# Sheet2.net
KiCad netlist of a schematic drawn in Altium Designer
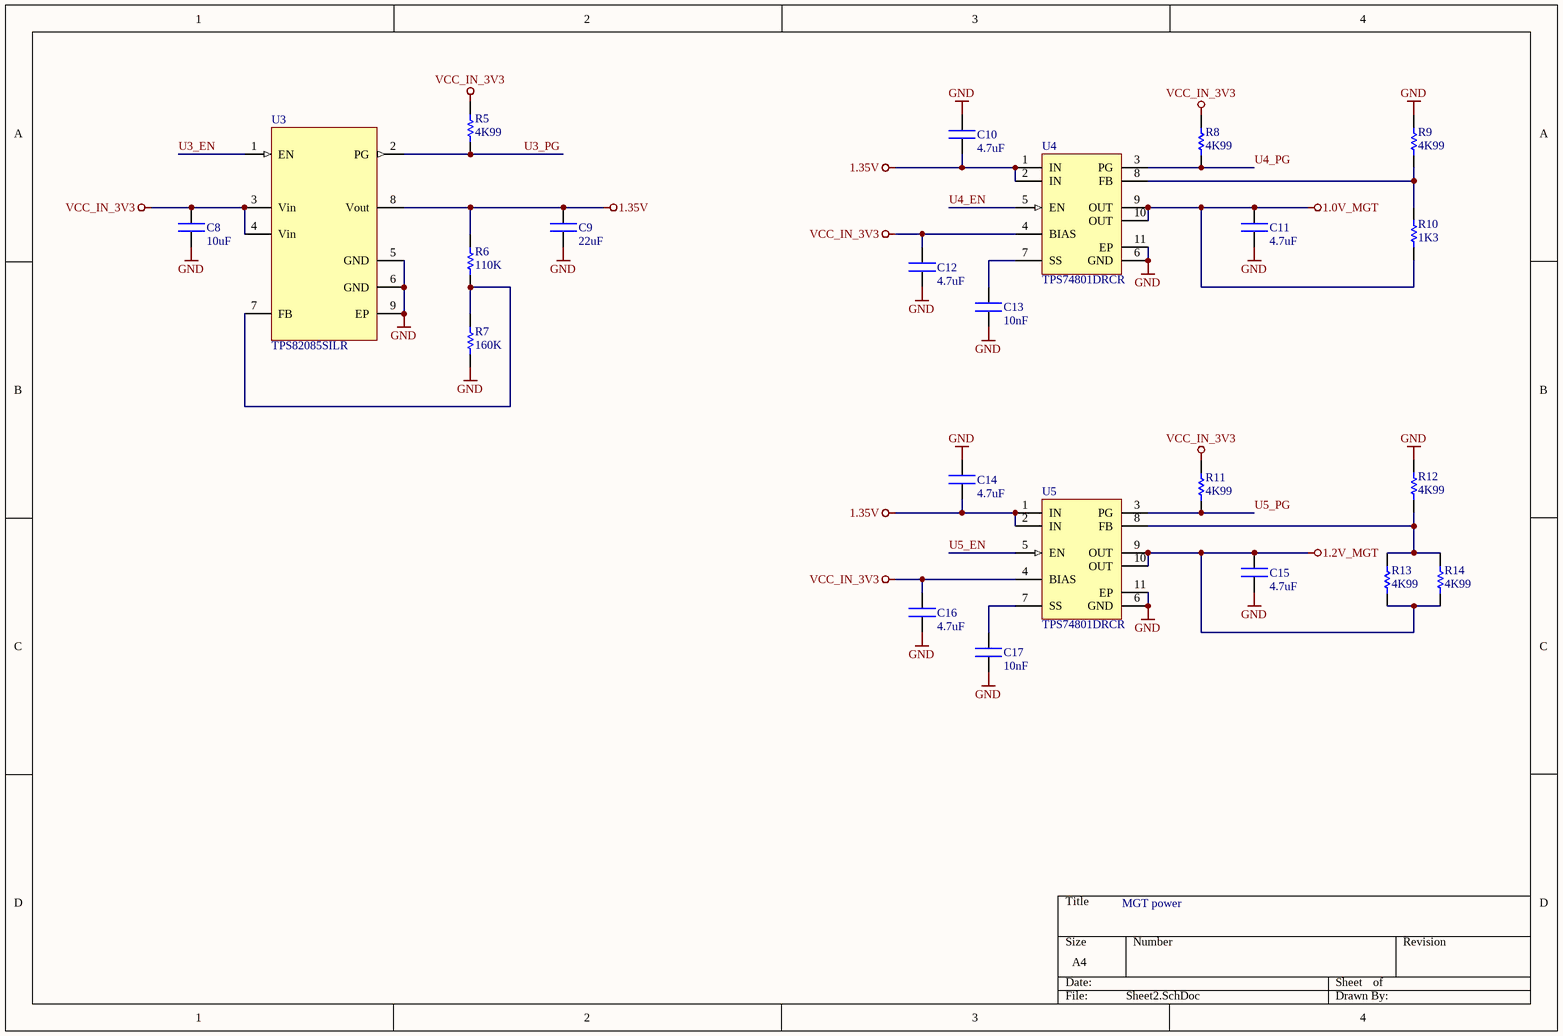
[diagram p0: Sheet2.SchDoc]

(export (version "E")
  (design (tool "Eeschema 10.0.6"))
  (components
    (comp (ref "C8")
      (value "10uF")
      (footprint "CAPC1608X08N")
      (description "Ceramic Chip Capacitor")
      (libsource (lib "Integrated_Library") (part "C0603"))
    )
    (comp (ref "C9")
      (value "22uF")
      (footprint "CAPC1608X08N")
      (description "Ceramic Chip Capacitor")
      (libsource (lib "Integrated_Library") (part "C0603"))
    )
    (comp (ref "C10")
      (value "4.7uF")
      (footprint "CAPC1005X05N")
      (description "Ceramic Chip Capacitor")
      (libsource (lib "Integrated_Library") (part "C0402"))
    )
    (comp (ref "C11")
      (value "4.7uF")
      (footprint "CAPC1005X05N")
      (description "Ceramic Chip Capacitor")
      (libsource (lib "Integrated_Library") (part "C0402"))
    )
    (comp (ref "C12")
      (value "4.7uF")
      (footprint "CAPC1005X05N")
      (description "Ceramic Chip Capacitor")
      (libsource (lib "Integrated_Library") (part "C0402"))
    )
    (comp (ref "C13")
      (value "10nF")
      (footprint "CAPC1005X05N")
      (description "Ceramic Chip Capacitor")
      (libsource (lib "Integrated_Library") (part "C0402"))
    )
    (comp (ref "C14")
      (value "4.7uF")
      (footprint "CAPC1005X05N")
      (description "Ceramic Chip Capacitor")
      (libsource (lib "Integrated_Library") (part "C0402"))
    )
    (comp (ref "C15")
      (value "4.7uF")
      (footprint "CAPC1005X05N")
      (description "Ceramic Chip Capacitor")
      (libsource (lib "Integrated_Library") (part "C0402"))
    )
    (comp (ref "C16")
      (value "4.7uF")
      (footprint "CAPC1005X05N")
      (description "Ceramic Chip Capacitor")
      (libsource (lib "Integrated_Library") (part "C0402"))
    )
    (comp (ref "C17")
      (value "10nF")
      (footprint "CAPC1005X05N")
      (description "Ceramic Chip Capacitor")
      (libsource (lib "Integrated_Library") (part "C0402"))
    )
    (comp (ref "R5")
      (value "4K99")
      (footprint "RESC1005X05N")
      (description "Ceramic Chip Resistor")
      (libsource (lib "Integrated_Library") (part "R0402"))
    )
    (comp (ref "R6")
      (value "110K")
      (footprint "RESC1005X05N")
      (description "Ceramic Chip Resistor")
      (libsource (lib "Integrated_Library") (part "R0402"))
    )
    (comp (ref "R7")
      (value "160K")
      (footprint "RESC1005X05N")
      (description "Ceramic Chip Resistor")
      (libsource (lib "Integrated_Library") (part "R0402"))
    )
    (comp (ref "R8")
      (value "4K99")
      (footprint "RESC1005X05N")
      (description "Ceramic Chip Resistor")
      (libsource (lib "Integrated_Library") (part "R0402"))
    )
    (comp (ref "R9")
      (value "4K99")
      (footprint "RESC1005X05N")
      (description "Ceramic Chip Resistor")
      (libsource (lib "Integrated_Library") (part "R0402"))
    )
    (comp (ref "R10")
      (value "1K3")
      (footprint "RESC1005X05N")
      (description "Ceramic Chip Resistor")
      (libsource (lib "Integrated_Library") (part "R0402"))
    )
    (comp (ref "R11")
      (value "4K99")
      (footprint "RESC1005X05N")
      (description "Ceramic Chip Resistor")
      (libsource (lib "Integrated_Library") (part "R0402"))
    )
    (comp (ref "R12")
      (value "4K99")
      (footprint "RESC1005X05N")
      (description "Ceramic Chip Resistor")
      (libsource (lib "Integrated_Library") (part "R0402"))
    )
    (comp (ref "R13")
      (value "4K99")
      (footprint "RESC1005X05N")
      (description "Ceramic Chip Resistor")
      (libsource (lib "Integrated_Library") (part "R0402"))
    )
    (comp (ref "R14")
      (value "4K99")
      (footprint "RESC1005X05N")
      (description "Ceramic Chip Resistor")
      (libsource (lib "Integrated_Library") (part "R0402"))
    )
    (comp (ref "U3")
      (value "TPS82085SILR")
      (footprint "TPS82085SILR")
      (description "3-A High Efficiency Step-Down Converter")
      (libsource (lib "Integrated_Library") (part "TPS82085SILR"))
    )
    (comp (ref "U4")
      (value "TPS74801DRCR")
      (footprint "TPS74801DRCR")
      (fields (field (name "MANUFACTURER") "Texas Instruments"))
      (libsource (lib "Integrated_Library") (part "TPS74801DRCR"))
    )
    (comp (ref "U5")
      (value "TPS74801DRCR")
      (footprint "TPS74801DRCR")
      (fields (field (name "MANUFACTURER") "Texas Instruments"))
      (libsource (lib "Integrated_Library") (part "TPS74801DRCR"))
    )
  )
  (nets
    (net (code "1") (name "/U3_EN") (class "Default")
      (node (ref "U3") (pin "1") (pinfunction "EN_1") (pintype "input"))
    )
    (net (code "2") (name "/U3_PG") (class "Default")
      (node (ref "R5") (pin "1") (pinfunction "1_1") (pintype "passive"))
      (node (ref "U3") (pin "2") (pinfunction "PG_2") (pintype "output"))
    )
    (net (code "3") (name "/U4_EN") (class "Default")
      (node (ref "U4") (pin "5") (pinfunction "EN_5") (pintype "input"))
    )
    (net (code "4") (name "/U4_PG") (class "Default")
      (node (ref "R8") (pin "1") (pinfunction "1_1") (pintype "passive"))
      (node (ref "U4") (pin "3") (pinfunction "PG_3") (pintype "tri_state"))
    )
    (net (code "5") (name "/U5_EN") (class "Default")
      (node (ref "U5") (pin "5") (pinfunction "EN_5") (pintype "input"))
    )
    (net (code "6") (name "/U5_PG") (class "Default")
      (node (ref "R11") (pin "1") (pinfunction "1_1") (pintype "passive"))
      (node (ref "U5") (pin "3") (pinfunction "PG_3") (pintype "tri_state"))
    )
    (net (code "7") (name "1.0V_MGT") (class "Default")
      (node (ref "C11") (pin "2") (pinfunction "2_2") (pintype "passive"))
      (node (ref "R10") (pin "2") (pinfunction "2_2") (pintype "passive"))
      (node (ref "U4") (pin "10") (pinfunction "OUT_10") (pintype "power_in"))
      (node (ref "U4") (pin "9") (pinfunction "OUT_9") (pintype "power_in"))
    )
    (net (code "8") (name "1.2V_MGT") (class "Default")
      (node (ref "C15") (pin "2") (pinfunction "2_2") (pintype "passive"))
      (node (ref "R13") (pin "1") (pinfunction "1_1") (pintype "passive"))
      (node (ref "R14") (pin "1") (pinfunction "1_1") (pintype "passive"))
      (node (ref "U5") (pin "10") (pinfunction "OUT_10") (pintype "power_in"))
      (node (ref "U5") (pin "9") (pinfunction "OUT_9") (pintype "power_in"))
    )
    (net (code "9") (name "1.35V") (class "Default")
      (node (ref "C10") (pin "2") (pinfunction "2_2") (pintype "passive"))
      (node (ref "C14") (pin "2") (pinfunction "2_2") (pintype "passive"))
      (node (ref "C9") (pin "2") (pinfunction "2_2") (pintype "passive"))
      (node (ref "R6") (pin "2") (pinfunction "2_2") (pintype "passive"))
      (node (ref "U3") (pin "8") (pinfunction "Vout_8") (pintype "power_in"))
      (node (ref "U4") (pin "1") (pinfunction "IN_1") (pintype "power_in"))
      (node (ref "U4") (pin "2") (pinfunction "IN_2") (pintype "power_in"))
      (node (ref "U5") (pin "1") (pinfunction "IN_1") (pintype "power_in"))
      (node (ref "U5") (pin "2") (pinfunction "IN_2") (pintype "power_in"))
    )
    (net (code "10") (name "GND") (class "Default")
      (node (ref "C10") (pin "1") (pinfunction "1_1") (pintype "passive"))
      (node (ref "C11") (pin "1") (pinfunction "1_1") (pintype "passive"))
      (node (ref "C12") (pin "1") (pinfunction "1_1") (pintype "passive"))
      (node (ref "C13") (pin "1") (pinfunction "1_1") (pintype "passive"))
      (node (ref "C14") (pin "1") (pinfunction "1_1") (pintype "passive"))
      (node (ref "C15") (pin "1") (pinfunction "1_1") (pintype "passive"))
      (node (ref "C16") (pin "1") (pinfunction "1_1") (pintype "passive"))
      (node (ref "C17") (pin "1") (pinfunction "1_1") (pintype "passive"))
      (node (ref "C8") (pin "1") (pinfunction "1_1") (pintype "passive"))
      (node (ref "C9") (pin "1") (pinfunction "1_1") (pintype "passive"))
      (node (ref "R12") (pin "1") (pinfunction "1_1") (pintype "passive"))
      (node (ref "R7") (pin "1") (pinfunction "1_1") (pintype "passive"))
      (node (ref "R9") (pin "2") (pinfunction "2_2") (pintype "passive"))
      (node (ref "U3") (pin "5") (pinfunction "GND_5") (pintype "power_in"))
      (node (ref "U3") (pin "6") (pinfunction "GND_6") (pintype "power_in"))
      (node (ref "U3") (pin "9") (pinfunction "EP_9") (pintype "power_in"))
      (node (ref "U4") (pin "11") (pinfunction "EP_11") (pintype "power_in"))
      (node (ref "U4") (pin "6") (pinfunction "GND_6") (pintype "power_in"))
      (node (ref "U5") (pin "11") (pinfunction "EP_11") (pintype "power_in"))
      (node (ref "U5") (pin "6") (pinfunction "GND_6") (pintype "power_in"))
    )
    (net (code "11") (name "Net-(U3-FB)") (class "Default")
      (node (ref "R6") (pin "1") (pinfunction "1_1") (pintype "passive"))
      (node (ref "R7") (pin "2") (pinfunction "2_2") (pintype "passive"))
      (node (ref "U3") (pin "7") (pinfunction "FB_7") (pintype "passive"))
    )
    (net (code "12") (name "Net-(U4-FB)") (class "Default")
      (node (ref "R10") (pin "1") (pinfunction "1_1") (pintype "passive"))
      (node (ref "R9") (pin "1") (pinfunction "1_1") (pintype "passive"))
      (node (ref "U4") (pin "8") (pinfunction "FB_8") (pintype "passive"))
    )
    (net (code "13") (name "Net-(U4-SS)") (class "Default")
      (node (ref "C13") (pin "2") (pinfunction "2_2") (pintype "passive"))
      (node (ref "U4") (pin "7") (pinfunction "SS_7") (pintype "passive"))
    )
    (net (code "14") (name "Net-(U5-FB)") (class "Default")
      (node (ref "R12") (pin "2") (pinfunction "2_2") (pintype "passive"))
      (node (ref "R13") (pin "2") (pinfunction "2_2") (pintype "passive"))
      (node (ref "R14") (pin "2") (pinfunction "2_2") (pintype "passive"))
      (node (ref "U5") (pin "8") (pinfunction "FB_8") (pintype "passive"))
    )
    (net (code "15") (name "Net-(U5-SS)") (class "Default")
      (node (ref "C17") (pin "2") (pinfunction "2_2") (pintype "passive"))
      (node (ref "U5") (pin "7") (pinfunction "SS_7") (pintype "passive"))
    )
    (net (code "16") (name "VCC_IN_3V3") (class "Default")
      (node (ref "C12") (pin "2") (pinfunction "2_2") (pintype "passive"))
      (node (ref "C16") (pin "2") (pinfunction "2_2") (pintype "passive"))
      (node (ref "C8") (pin "2") (pinfunction "2_2") (pintype "passive"))
      (node (ref "R11") (pin "2") (pinfunction "2_2") (pintype "passive"))
      (node (ref "R5") (pin "2") (pinfunction "2_2") (pintype "passive"))
      (node (ref "R8") (pin "2") (pinfunction "2_2") (pintype "passive"))
      (node (ref "U3") (pin "3") (pinfunction "Vin_3") (pintype "power_in"))
      (node (ref "U3") (pin "4") (pinfunction "Vin_4") (pintype "power_in"))
      (node (ref "U4") (pin "4") (pinfunction "BIAS_4") (pintype "power_in"))
      (node (ref "U5") (pin "4") (pinfunction "BIAS_4") (pintype "power_in"))
    )
  )
)
